# integration_test_board.net
KiCad netlist of a schematic drawn in EAGLE
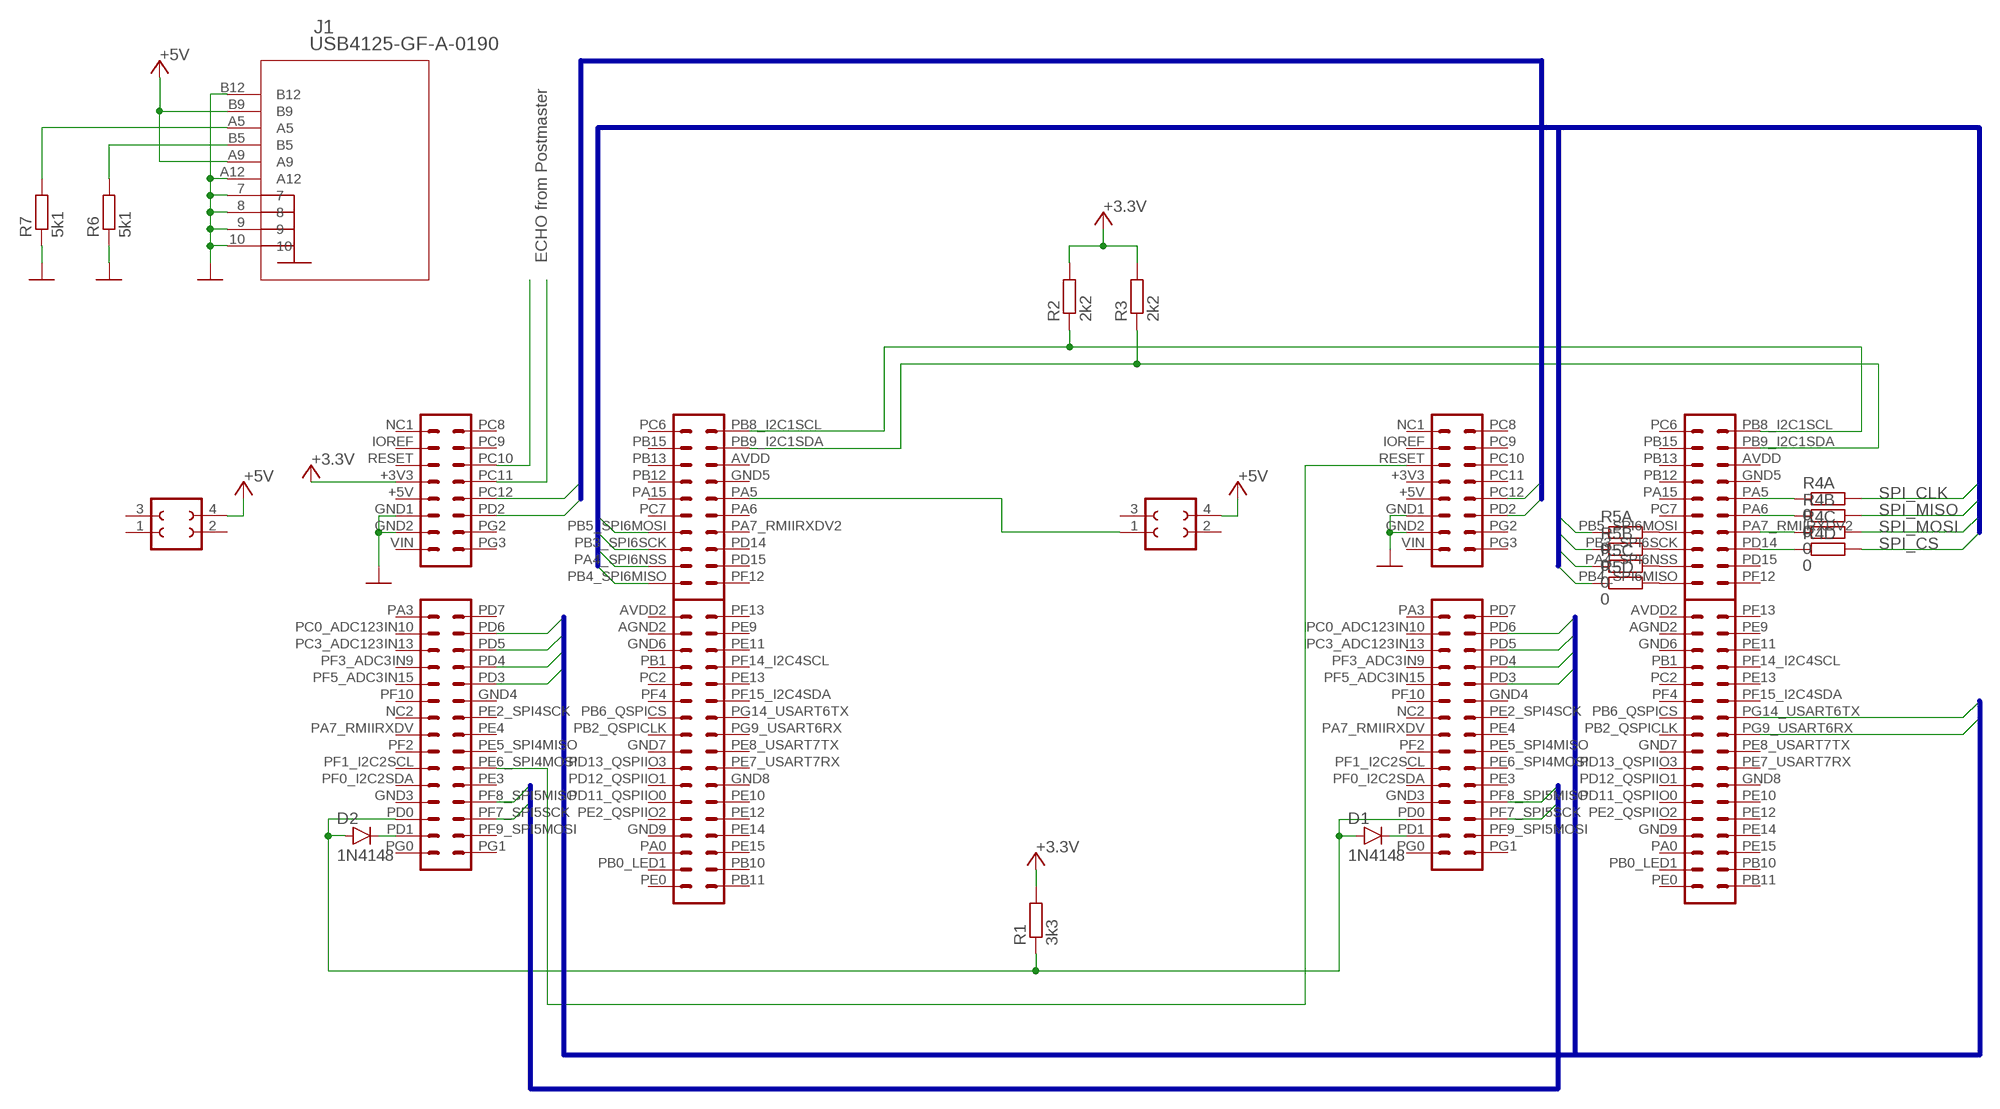
[diagram p0: schematic, sheet 1]

(export (version "E")
  (design (tool "Eeschema 10.0.6"))
  (components
    (comp (ref "D1")
      (value "1N4148")
      (footprint "eagle-import:MINIMELF")
      (libsource (lib "eagle-import") (part "1N4148"))
    )
    (comp (ref "D2")
      (value "1N4148")
      (footprint "eagle-import:MINIMELF")
      (libsource (lib "eagle-import") (part "1N4148"))
    )
    (comp (ref "J1")
      (value "USB4125-GF-A-0190")
      (footprint "eagle-import:CONN6_125-GF-A-0190_GCT")
      (fields (field (name "COPYRIGHT") "Copyright (C) 2023 Ultra Librarian. All rights reserved."))
      (libsource (lib "eagle-import") (part "USB4125-GF-A-0190"))
    )
    (comp (ref "R1")
      (value "3k3")
      (footprint "eagle-import:0805")
      (libsource (lib "eagle-import") (part "RESISTORR0805"))
    )
    (comp (ref "R2")
      (value "2k2")
      (footprint "eagle-import:0805")
      (libsource (lib "eagle-import") (part "RESISTORR0805"))
    )
    (comp (ref "R3")
      (value "2k2")
      (footprint "eagle-import:0805")
      (libsource (lib "eagle-import") (part "RESISTORR0805"))
    )
    (comp (ref "R4")
      (value "0")
      (footprint "eagle-import:ARRAY0603X4")
      (libsource (lib "eagle-import") (part "ARRAY-4RESISTOR"))
    )
    (comp (ref "R5")
      (value "0")
      (footprint "eagle-import:ARRAY0603X4")
      (libsource (lib "eagle-import") (part "ARRAY-4RESISTOR"))
    )
    (comp (ref "R6")
      (value "5k1")
      (footprint "eagle-import:0805")
      (libsource (lib "eagle-import") (part "RESISTORR0805"))
    )
    (comp (ref "R7")
      (value "5k1")
      (footprint "eagle-import:0805")
      (libsource (lib "eagle-import") (part "RESISTORR0805"))
    )
    (comp (ref "U$1")
      (value "NUCLEO-767")
      (footprint "eagle-import:NUCLEO-767")
      (libsource (lib "eagle-import") (part "NUCLEO-767"))
    )
    (comp (ref "U$2")
      (value "NUCLEO-767")
      (footprint "eagle-import:NUCLEO-767")
      (libsource (lib "eagle-import") (part "NUCLEO-767"))
    )
    (comp (ref "U$4")
      (value "HEADER-FEMALE-2-2")
      (footprint "eagle-import:HEADER-FEMALE-2-2")
      (libsource (lib "eagle-import") (part "HEADER-FEMALE-2-2"))
    )
    (comp (ref "U$5")
      (value "HEADER-FEMALE-2-2")
      (footprint "eagle-import:HEADER-FEMALE-2-2")
      (libsource (lib "eagle-import") (part "HEADER-FEMALE-2-2"))
    )
  )
  (nets
    (net (code "1") (name "+3.3V") (class "Default")
      (node (ref "R1") (pin "2") (pinfunction "2_2") (pintype "passive"))
      (node (ref "R2") (pin "2") (pinfunction "2_2") (pintype "passive"))
      (node (ref "R3") (pin "2") (pinfunction "2_2") (pintype "passive"))
      (node (ref "U$1") (pin "+3V3") (pinfunction "7_+3V3") (pintype "passive"))
    )
    (net (code "2") (name "+5V") (class "Default")
      (node (ref "J1") (pin "A9") (pinfunction "A9_A9") (pintype "passive"))
      (node (ref "J1") (pin "B9") (pinfunction "B9_B9") (pintype "passive"))
      (node (ref "U$4") (pin "4") (pinfunction "4_4") (pintype "passive"))
      (node (ref "U$5") (pin "4") (pinfunction "4_4") (pintype "passive"))
    )
    (net (code "3") (name "/ECHO_RX") (class "Default")
      (node (ref "U$1") (pin "PC12") (pinfunction "10_PC12") (pintype "passive"))
      (node (ref "U$2") (pin "PD2") (pinfunction "12_PD2") (pintype "passive"))
    )
    (net (code "4") (name "/ECHO_TX") (class "Default")
      (node (ref "U$1") (pin "PD2") (pinfunction "12_PD2") (pintype "passive"))
      (node (ref "U$2") (pin "PC12") (pinfunction "10_PC12") (pintype "passive"))
    )
    (net (code "5") (name "/GPIO_IN") (class "Default")
      (node (ref "U$1") (pin "PF7_SPI5SCK") (pinfunction "26_PF7_SPI5SCK") (pintype "passive"))
      (node (ref "U$2") (pin "PF7_SPI5SCK") (pinfunction "26_PF7_SPI5SCK") (pintype "passive"))
    )
    (net (code "6") (name "/GPIO_OUT") (class "Default")
      (node (ref "U$1") (pin "PF8_SPI5MISO") (pinfunction "24_PF8_SPI5MISO") (pintype "passive"))
      (node (ref "U$2") (pin "PF8_SPI5MISO") (pinfunction "24_PF8_SPI5MISO") (pintype "passive"))
    )
    (net (code "7") (name "/SPI_CLK") (class "Default")
      (node (ref "R4") (pin "8") (pinfunction "2_8") (pintype "passive"))
      (node (ref "R5") (pin "2") (pinfunction "1_2") (pintype "passive"))
      (node (ref "U$1") (pin "PB3_SPI6SCK") (pinfunction "15_PB3_SPI6SCK") (pintype "passive"))
    )
    (net (code "8") (name "/SPI_CS") (class "Default")
      (node (ref "R4") (pin "5") (pinfunction "2_5") (pintype "passive"))
      (node (ref "R5") (pin "3") (pinfunction "1_3") (pintype "passive"))
      (node (ref "U$1") (pin "PA4_SPI6NSS") (pinfunction "17_PA4_SPI6NSS") (pintype "passive"))
    )
    (net (code "9") (name "/SPI_MISO") (class "Default")
      (node (ref "R4") (pin "7") (pinfunction "2_7") (pintype "passive"))
      (node (ref "R5") (pin "4") (pinfunction "1_4") (pintype "passive"))
      (node (ref "U$1") (pin "PB4_SPI6MISO") (pinfunction "19_PB4_SPI6MISO") (pintype "passive"))
    )
    (net (code "10") (name "/SPI_MOSI") (class "Default")
      (node (ref "R4") (pin "6") (pinfunction "2_6") (pintype "passive"))
      (node (ref "R5") (pin "1") (pinfunction "1_1") (pintype "passive"))
      (node (ref "U$1") (pin "PB5_SPI6MOSI") (pinfunction "13_PB5_SPI6MOSI") (pintype "passive"))
    )
    (net (code "11") (name "/UART_CTS") (class "Default")
      (node (ref "U$1") (pin "PD4") (pinfunction "8_PD4") (pintype "passive"))
      (node (ref "U$2") (pin "PD3") (pinfunction "10_PD3") (pintype "passive"))
    )
    (net (code "12") (name "/UART_RTR") (class "Default")
      (node (ref "U$1") (pin "PD3") (pinfunction "10_PD3") (pintype "passive"))
      (node (ref "U$2") (pin "PD4") (pinfunction "8_PD4") (pintype "passive"))
    )
    (net (code "13") (name "/UART_RX") (class "Default")
      (node (ref "U$1") (pin "PD5") (pinfunction "6_PD5") (pintype "passive"))
      (node (ref "U$2") (pin "PD6") (pinfunction "4_PD6") (pintype "passive"))
      (node (ref "U$2") (pin "PG9_USART6RX") (pinfunction "16_PG9_USART6RX") (pintype "passive"))
    )
    (net (code "14") (name "/UART_TX") (class "Default")
      (node (ref "U$1") (pin "PD6") (pinfunction "4_PD6") (pintype "passive"))
      (node (ref "U$2") (pin "PD5") (pinfunction "6_PD5") (pintype "passive"))
      (node (ref "U$2") (pin "PG14_USART6TX") (pinfunction "14_PG14_USART6TX") (pintype "passive"))
    )
    (net (code "15") (name "0V") (class "Default")
      (node (ref "J1") (pin "10") (pinfunction "10_10") (pintype "passive"))
      (node (ref "J1") (pin "7") (pinfunction "7_7") (pintype "passive"))
      (node (ref "J1") (pin "8") (pinfunction "8_8") (pintype "passive"))
      (node (ref "J1") (pin "9") (pinfunction "9_9") (pintype "passive"))
      (node (ref "J1") (pin "A12") (pinfunction "A12_A12") (pintype "passive"))
      (node (ref "J1") (pin "B12") (pinfunction "B12_B12") (pintype "passive"))
      (node (ref "R6") (pin "1") (pinfunction "1_1") (pintype "passive"))
      (node (ref "R7") (pin "1") (pinfunction "1_1") (pintype "passive"))
      (node (ref "U$1") (pin "GND1") (pinfunction "11_GND1") (pintype "passive"))
      (node (ref "U$1") (pin "GND2") (pinfunction "13_GND2") (pintype "passive"))
      (node (ref "U$2") (pin "GND1") (pinfunction "11_GND1") (pintype "passive"))
      (node (ref "U$2") (pin "GND2") (pinfunction "13_GND2") (pintype "passive"))
    )
    (net (code "16") (name "Net-(J1-PadA5)") (class "Default")
      (node (ref "J1") (pin "A5") (pinfunction "A5_A5") (pintype "passive"))
      (node (ref "R7") (pin "2") (pinfunction "2_2") (pintype "passive"))
    )
    (net (code "17") (name "Net-(J1-PadB5)") (class "Default")
      (node (ref "J1") (pin "B5") (pinfunction "B5_B5") (pintype "passive"))
      (node (ref "R6") (pin "2") (pinfunction "2_2") (pintype "passive"))
    )
    (net (code "18") (name "Net-(R4B-1)") (class "Default")
      (node (ref "R4") (pin "2") (pinfunction "1_2") (pintype "passive"))
      (node (ref "U$2") (pin "PA6") (pinfunction "12_PA6") (pintype "passive"))
    )
    (net (code "19") (name "Net-(R4C-1)") (class "Default")
      (node (ref "R4") (pin "3") (pinfunction "1_3") (pintype "passive"))
      (node (ref "U$2") (pin "PA7_RMIIRXDV2") (pinfunction "14_PA7_RMIIRXDV2") (pintype "passive"))
    )
    (net (code "20") (name "Net-(R4D-1)") (class "Default")
      (node (ref "R4") (pin "4") (pinfunction "1_4") (pintype "passive"))
      (node (ref "U$2") (pin "PD14") (pinfunction "16_PD14") (pintype "passive"))
    )
    (net (code "21") (name "Net-(R5A-2)") (class "Default")
      (node (ref "R5") (pin "8") (pinfunction "2_8") (pintype "passive"))
      (node (ref "U$2") (pin "PB5_SPI6MOSI") (pinfunction "13_PB5_SPI6MOSI") (pintype "passive"))
    )
    (net (code "22") (name "Net-(R5B-2)") (class "Default")
      (node (ref "R5") (pin "7") (pinfunction "2_7") (pintype "passive"))
      (node (ref "U$2") (pin "PB3_SPI6SCK") (pinfunction "15_PB3_SPI6SCK") (pintype "passive"))
    )
    (net (code "23") (name "Net-(R5C-2)") (class "Default")
      (node (ref "R5") (pin "6") (pinfunction "2_6") (pintype "passive"))
      (node (ref "U$2") (pin "PA4_SPI6NSS") (pinfunction "17_PA4_SPI6NSS") (pintype "passive"))
    )
    (net (code "24") (name "Net-(R5D-2)") (class "Default")
      (node (ref "R5") (pin "5") (pinfunction "2_5") (pintype "passive"))
      (node (ref "U$2") (pin "PB4_SPI6MISO") (pinfunction "19_PB4_SPI6MISO") (pintype "passive"))
    )
    (net (code "25") (name "Net-(U$1B-20)") (class "Default")
      (node (ref "U$1") (pin "PE6_SPI4MOSI") (pinfunction "20_PE6_SPI4MOSI") (pintype "passive"))
      (node (ref "U$2") (pin "RESET") (pinfunction "5_RESET") (pintype "passive"))
    )
    (net (code "26") (name "Net-(U$1B-25)") (class "Default")
      (node (ref "D1") (pin "A") (pinfunction "A_A") (pintype "passive"))
      (node (ref "D2") (pin "A") (pinfunction "A_A") (pintype "passive"))
      (node (ref "R1") (pin "1") (pinfunction "1_1") (pintype "passive"))
      (node (ref "U$1") (pin "PD0") (pinfunction "25_PD0") (pintype "passive"))
      (node (ref "U$2") (pin "PD0") (pinfunction "25_PD0") (pintype "passive"))
    )
    (net (code "27") (name "Net-(U$1B-27)") (class "Default")
      (node (ref "D2") (pin "C") (pinfunction "C_C") (pintype "passive"))
      (node (ref "U$1") (pin "PD1") (pinfunction "27_PD1") (pintype "passive"))
    )
    (net (code "28") (name "Net-(U$1C-2)") (class "Default")
      (node (ref "R2") (pin "1") (pinfunction "1_1") (pintype "passive"))
      (node (ref "U$1") (pin "PB8_I2C1SCL") (pinfunction "2_PB8_I2C1SCL") (pintype "passive"))
      (node (ref "U$2") (pin "PB8_I2C1SCL") (pinfunction "2_PB8_I2C1SCL") (pintype "passive"))
    )
    (net (code "29") (name "Net-(U$1C-4)") (class "Default")
      (node (ref "R3") (pin "1") (pinfunction "1_1") (pintype "passive"))
      (node (ref "U$1") (pin "PB9_I2C1SDA") (pinfunction "4_PB9_I2C1SDA") (pintype "passive"))
      (node (ref "U$2") (pin "PB9_I2C1SDA") (pinfunction "4_PB9_I2C1SDA") (pintype "passive"))
    )
    (net (code "30") (name "Net-(U$1C-10)") (class "Default")
      (node (ref "U$1") (pin "PA5") (pinfunction "10_PA5") (pintype "passive"))
      (node (ref "U$4") (pin "1") (pinfunction "1_1") (pintype "passive"))
    )
    (net (code "31") (name "Net-(U$2B-27)") (class "Default")
      (node (ref "D1") (pin "C") (pinfunction "C_C") (pintype "passive"))
      (node (ref "U$2") (pin "PD1") (pinfunction "27_PD1") (pintype "passive"))
    )
    (net (code "32") (name "Net-(U$2C-10)") (class "Default")
      (node (ref "R4") (pin "1") (pinfunction "1_1") (pintype "passive"))
      (node (ref "U$2") (pin "PA5") (pinfunction "10_PA5") (pintype "passive"))
    )
    (net (code "33") (name "unconnected-(U$1A-1-PadNC1)") (class "Default")
      (node (ref "U$1") (pin "NC1") (pinfunction "1_NC1") (pintype "passive"))
    )
    (net (code "34") (name "unconnected-(U$1A-2-PadPC8)") (class "Default")
      (node (ref "U$1") (pin "PC8") (pinfunction "2_PC8") (pintype "passive"))
    )
    (net (code "35") (name "unconnected-(U$1A-3-PadIOREF)") (class "Default")
      (node (ref "U$1") (pin "IOREF") (pinfunction "3_IOREF") (pintype "passive"))
    )
    (net (code "36") (name "unconnected-(U$1A-4-PadPC9)") (class "Default")
      (node (ref "U$1") (pin "PC9") (pinfunction "4_PC9") (pintype "passive"))
    )
    (net (code "37") (name "unconnected-(U$1A-5-PadRESET)") (class "Default")
      (node (ref "U$1") (pin "RESET") (pinfunction "5_RESET") (pintype "passive"))
    )
    (net (code "38") (name "unconnected-(U$1A-6-PadPC10)") (class "Default")
      (node (ref "U$1") (pin "PC10") (pinfunction "6_PC10") (pintype "passive"))
    )
    (net (code "39") (name "unconnected-(U$1A-8-PadPC11)") (class "Default")
      (node (ref "U$1") (pin "PC11") (pinfunction "8_PC11") (pintype "passive"))
    )
    (net (code "40") (name "unconnected-(U$1A-9-Pad+5V)") (class "Default")
      (node (ref "U$1") (pin "+5V") (pinfunction "9_+5V") (pintype "passive"))
    )
    (net (code "41") (name "unconnected-(U$1A-14-PadPG2)") (class "Default")
      (node (ref "U$1") (pin "PG2") (pinfunction "14_PG2") (pintype "passive"))
    )
    (net (code "42") (name "unconnected-(U$1A-15-PadVIN)") (class "Default")
      (node (ref "U$1") (pin "VIN") (pinfunction "15_VIN") (pintype "passive"))
    )
    (net (code "43") (name "unconnected-(U$1A-16-PadPG3)") (class "Default")
      (node (ref "U$1") (pin "PG3") (pinfunction "16_PG3") (pintype "passive"))
    )
    (net (code "44") (name "unconnected-(U$1B-1-PadPA3)") (class "Default")
      (node (ref "U$1") (pin "PA3") (pinfunction "1_PA3") (pintype "passive"))
    )
    (net (code "45") (name "unconnected-(U$1B-2-PadPD7)") (class "Default")
      (node (ref "U$1") (pin "PD7") (pinfunction "2_PD7") (pintype "passive"))
    )
    (net (code "46") (name "unconnected-(U$1B-3-PadPC0_ADC123IN10)") (class "Default")
      (node (ref "U$1") (pin "PC0_ADC123IN10") (pinfunction "3_PC0_ADC123IN10") (pintype "passive"))
    )
    (net (code "47") (name "unconnected-(U$1B-5-PadPC3_ADC123IN13)") (class "Default")
      (node (ref "U$1") (pin "PC3_ADC123IN13") (pinfunction "5_PC3_ADC123IN13") (pintype "passive"))
    )
    (net (code "48") (name "unconnected-(U$1B-7-PadPF3_ADC3IN9)") (class "Default")
      (node (ref "U$1") (pin "PF3_ADC3IN9") (pinfunction "7_PF3_ADC3IN9") (pintype "passive"))
    )
    (net (code "49") (name "unconnected-(U$1B-9-PadPF5_ADC3IN15)") (class "Default")
      (node (ref "U$1") (pin "PF5_ADC3IN15") (pinfunction "9_PF5_ADC3IN15") (pintype "passive"))
    )
    (net (code "50") (name "unconnected-(U$1B-11-PadPF10)") (class "Default")
      (node (ref "U$1") (pin "PF10") (pinfunction "11_PF10") (pintype "passive"))
    )
    (net (code "51") (name "unconnected-(U$1B-12-PadGND4)") (class "Default")
      (node (ref "U$1") (pin "GND4") (pinfunction "12_GND4") (pintype "passive"))
    )
    (net (code "52") (name "unconnected-(U$1B-13-PadNC2)") (class "Default")
      (node (ref "U$1") (pin "NC2") (pinfunction "13_NC2") (pintype "passive"))
    )
    (net (code "53") (name "unconnected-(U$1B-14-PadPE2_SPI4SCK)") (class "Default")
      (node (ref "U$1") (pin "PE2_SPI4SCK") (pinfunction "14_PE2_SPI4SCK") (pintype "passive"))
    )
    (net (code "54") (name "unconnected-(U$1B-15-PadPA7_RMIIRXDV)") (class "Default")
      (node (ref "U$1") (pin "PA7_RMIIRXDV") (pinfunction "15_PA7_RMIIRXDV") (pintype "passive"))
    )
    (net (code "55") (name "unconnected-(U$1B-16-PadPE4)") (class "Default")
      (node (ref "U$1") (pin "PE4") (pinfunction "16_PE4") (pintype "passive"))
    )
    (net (code "56") (name "unconnected-(U$1B-17-PadPF2)") (class "Default")
      (node (ref "U$1") (pin "PF2") (pinfunction "17_PF2") (pintype "passive"))
    )
    (net (code "57") (name "unconnected-(U$1B-18-PadPE5_SPI4MISO)") (class "Default")
      (node (ref "U$1") (pin "PE5_SPI4MISO") (pinfunction "18_PE5_SPI4MISO") (pintype "passive"))
    )
    (net (code "58") (name "unconnected-(U$1B-19-PadPF1_I2C2SCL)") (class "Default")
      (node (ref "U$1") (pin "PF1_I2C2SCL") (pinfunction "19_PF1_I2C2SCL") (pintype "passive"))
    )
    (net (code "59") (name "unconnected-(U$1B-21-PadPF0_I2C2SDA)") (class "Default")
      (node (ref "U$1") (pin "PF0_I2C2SDA") (pinfunction "21_PF0_I2C2SDA") (pintype "passive"))
    )
    (net (code "60") (name "unconnected-(U$1B-22-PadPE3)") (class "Default")
      (node (ref "U$1") (pin "PE3") (pinfunction "22_PE3") (pintype "passive"))
    )
    (net (code "61") (name "unconnected-(U$1B-23-PadGND3)") (class "Default")
      (node (ref "U$1") (pin "GND3") (pinfunction "23_GND3") (pintype "passive"))
    )
    (net (code "62") (name "unconnected-(U$1B-28-PadPF9_SPI5MOSI)") (class "Default")
      (node (ref "U$1") (pin "PF9_SPI5MOSI") (pinfunction "28_PF9_SPI5MOSI") (pintype "passive"))
    )
    (net (code "63") (name "unconnected-(U$1B-29-PadPG0)") (class "Default")
      (node (ref "U$1") (pin "PG0") (pinfunction "29_PG0") (pintype "passive"))
    )
    (net (code "64") (name "unconnected-(U$1B-30-PadPG1)") (class "Default")
      (node (ref "U$1") (pin "PG1") (pinfunction "30_PG1") (pintype "passive"))
    )
    (net (code "65") (name "unconnected-(U$1C-1-PadPC6)") (class "Default")
      (node (ref "U$1") (pin "PC6") (pinfunction "1_PC6") (pintype "passive"))
    )
    (net (code "66") (name "unconnected-(U$1C-3-PadPB15)") (class "Default")
      (node (ref "U$1") (pin "PB15") (pinfunction "3_PB15") (pintype "passive"))
    )
    (net (code "67") (name "unconnected-(U$1C-5-PadPB13)") (class "Default")
      (node (ref "U$1") (pin "PB13") (pinfunction "5_PB13") (pintype "passive"))
    )
    (net (code "68") (name "unconnected-(U$1C-6-PadAVDD)") (class "Default")
      (node (ref "U$1") (pin "AVDD") (pinfunction "6_AVDD") (pintype "passive"))
    )
    (net (code "69") (name "unconnected-(U$1C-7-PadPB12)") (class "Default")
      (node (ref "U$1") (pin "PB12") (pinfunction "7_PB12") (pintype "passive"))
    )
    (net (code "70") (name "unconnected-(U$1C-8-PadGND5)") (class "Default")
      (node (ref "U$1") (pin "GND5") (pinfunction "8_GND5") (pintype "passive"))
    )
    (net (code "71") (name "unconnected-(U$1C-9-PadPA15)") (class "Default")
      (node (ref "U$1") (pin "PA15") (pinfunction "9_PA15") (pintype "passive"))
    )
    (net (code "72") (name "unconnected-(U$1C-11-PadPC7)") (class "Default")
      (node (ref "U$1") (pin "PC7") (pinfunction "11_PC7") (pintype "passive"))
    )
    (net (code "73") (name "unconnected-(U$1C-12-PadPA6)") (class "Default")
      (node (ref "U$1") (pin "PA6") (pinfunction "12_PA6") (pintype "passive"))
    )
    (net (code "74") (name "unconnected-(U$1C-14-PadPA7_RMIIRXDV2)") (class "Default")
      (node (ref "U$1") (pin "PA7_RMIIRXDV2") (pinfunction "14_PA7_RMIIRXDV2") (pintype "passive"))
    )
    (net (code "75") (name "unconnected-(U$1C-16-PadPD14)") (class "Default")
      (node (ref "U$1") (pin "PD14") (pinfunction "16_PD14") (pintype "passive"))
    )
    (net (code "76") (name "unconnected-(U$1C-18-PadPD15)") (class "Default")
      (node (ref "U$1") (pin "PD15") (pinfunction "18_PD15") (pintype "passive"))
    )
    (net (code "77") (name "unconnected-(U$1C-20-PadPF12)") (class "Default")
      (node (ref "U$1") (pin "PF12") (pinfunction "20_PF12") (pintype "passive"))
    )
    (net (code "78") (name "unconnected-(U$1D-1-PadAVDD2)") (class "Default")
      (node (ref "U$1") (pin "AVDD2") (pinfunction "1_AVDD2") (pintype "passive"))
    )
    (net (code "79") (name "unconnected-(U$1D-2-PadPF13)") (class "Default")
      (node (ref "U$1") (pin "PF13") (pinfunction "2_PF13") (pintype "passive"))
    )
    (net (code "80") (name "unconnected-(U$1D-3-PadAGND2)") (class "Default")
      (node (ref "U$1") (pin "AGND2") (pinfunction "3_AGND2") (pintype "passive"))
    )
    (net (code "81") (name "unconnected-(U$1D-4-PadPE9)") (class "Default")
      (node (ref "U$1") (pin "PE9") (pinfunction "4_PE9") (pintype "passive"))
    )
    (net (code "82") (name "unconnected-(U$1D-5-PadGND6)") (class "Default")
      (node (ref "U$1") (pin "GND6") (pinfunction "5_GND6") (pintype "passive"))
    )
    (net (code "83") (name "unconnected-(U$1D-6-PadPE11)") (class "Default")
      (node (ref "U$1") (pin "PE11") (pinfunction "6_PE11") (pintype "passive"))
    )
    (net (code "84") (name "unconnected-(U$1D-7-PadPB1)") (class "Default")
      (node (ref "U$1") (pin "PB1") (pinfunction "7_PB1") (pintype "passive"))
    )
    (net (code "85") (name "unconnected-(U$1D-8-PadPF14_I2C4SCL)") (class "Default")
      (node (ref "U$1") (pin "PF14_I2C4SCL") (pinfunction "8_PF14_I2C4SCL") (pintype "passive"))
    )
    (net (code "86") (name "unconnected-(U$1D-9-PadPC2)") (class "Default")
      (node (ref "U$1") (pin "PC2") (pinfunction "9_PC2") (pintype "passive"))
    )
    (net (code "87") (name "unconnected-(U$1D-10-PadPE13)") (class "Default")
      (node (ref "U$1") (pin "PE13") (pinfunction "10_PE13") (pintype "passive"))
    )
    (net (code "88") (name "unconnected-(U$1D-11-PadPF4)") (class "Default")
      (node (ref "U$1") (pin "PF4") (pinfunction "11_PF4") (pintype "passive"))
    )
    (net (code "89") (name "unconnected-(U$1D-12-PadPF15_I2C4SDA)") (class "Default")
      (node (ref "U$1") (pin "PF15_I2C4SDA") (pinfunction "12_PF15_I2C4SDA") (pintype "passive"))
    )
    (net (code "90") (name "unconnected-(U$1D-13-PadPB6_QSPICS)") (class "Default")
      (node (ref "U$1") (pin "PB6_QSPICS") (pinfunction "13_PB6_QSPICS") (pintype "passive"))
    )
    (net (code "91") (name "unconnected-(U$1D-14-PadPG14_USART6TX)") (class "Default")
      (node (ref "U$1") (pin "PG14_USART6TX") (pinfunction "14_PG14_USART6TX") (pintype "passive"))
    )
    (net (code "92") (name "unconnected-(U$1D-15-PadPB2_QSPICLK)") (class "Default")
      (node (ref "U$1") (pin "PB2_QSPICLK") (pinfunction "15_PB2_QSPICLK") (pintype "passive"))
    )
    (net (code "93") (name "unconnected-(U$1D-16-PadPG9_USART6RX)") (class "Default")
      (node (ref "U$1") (pin "PG9_USART6RX") (pinfunction "16_PG9_USART6RX") (pintype "passive"))
    )
    (net (code "94") (name "unconnected-(U$1D-17-PadGND7)") (class "Default")
      (node (ref "U$1") (pin "GND7") (pinfunction "17_GND7") (pintype "passive"))
    )
    (net (code "95") (name "unconnected-(U$1D-18-PadPE8_USART7TX)") (class "Default")
      (node (ref "U$1") (pin "PE8_USART7TX") (pinfunction "18_PE8_USART7TX") (pintype "passive"))
    )
    (net (code "96") (name "unconnected-(U$1D-19-PadPD13_QSPIIO3)") (class "Default")
      (node (ref "U$1") (pin "PD13_QSPIIO3") (pinfunction "19_PD13_QSPIIO3") (pintype "passive"))
    )
    (net (code "97") (name "unconnected-(U$1D-20-PadPE7_USART7RX)") (class "Default")
      (node (ref "U$1") (pin "PE7_USART7RX") (pinfunction "20_PE7_USART7RX") (pintype "passive"))
    )
    (net (code "98") (name "unconnected-(U$1D-21-PadPD12_QSPIIO1)") (class "Default")
      (node (ref "U$1") (pin "PD12_QSPIIO1") (pinfunction "21_PD12_QSPIIO1") (pintype "passive"))
    )
    (net (code "99") (name "unconnected-(U$1D-22-PadGND8)") (class "Default")
      (node (ref "U$1") (pin "GND8") (pinfunction "22_GND8") (pintype "passive"))
    )
    (net (code "100") (name "unconnected-(U$1D-23-PadPD11_QSPIIO0)") (class "Default")
      (node (ref "U$1") (pin "PD11_QSPIIO0") (pinfunction "23_PD11_QSPIIO0") (pintype "passive"))
    )
    (net (code "101") (name "unconnected-(U$1D-24-PadPE10)") (class "Default")
      (node (ref "U$1") (pin "PE10") (pinfunction "24_PE10") (pintype "passive"))
    )
    (net (code "102") (name "unconnected-(U$1D-25-PadPE2_QSPIIO2)") (class "Default")
      (node (ref "U$1") (pin "PE2_QSPIIO2") (pinfunction "25_PE2_QSPIIO2") (pintype "passive"))
    )
    (net (code "103") (name "unconnected-(U$1D-26-PadPE12)") (class "Default")
      (node (ref "U$1") (pin "PE12") (pinfunction "26_PE12") (pintype "passive"))
    )
    (net (code "104") (name "unconnected-(U$1D-27-PadGND9)") (class "Default")
      (node (ref "U$1") (pin "GND9") (pinfunction "27_GND9") (pintype "passive"))
    )
    (net (code "105") (name "unconnected-(U$1D-28-PadPE14)") (class "Default")
      (node (ref "U$1") (pin "PE14") (pinfunction "28_PE14") (pintype "passive"))
    )
    (net (code "106") (name "unconnected-(U$1D-29-PadPA0)") (class "Default")
      (node (ref "U$1") (pin "PA0") (pinfunction "29_PA0") (pintype "passive"))
    )
    (net (code "107") (name "unconnected-(U$1D-30-PadPE15)") (class "Default")
      (node (ref "U$1") (pin "PE15") (pinfunction "30_PE15") (pintype "passive"))
    )
    (net (code "108") (name "unconnected-(U$1D-31-PadPB0_LED1)") (class "Default")
      (node (ref "U$1") (pin "PB0_LED1") (pinfunction "31_PB0_LED1") (pintype "passive"))
    )
    (net (code "109") (name "unconnected-(U$1D-32-PadPB10)") (class "Default")
      (node (ref "U$1") (pin "PB10") (pinfunction "32_PB10") (pintype "passive"))
    )
    (net (code "110") (name "unconnected-(U$1D-33-PadPE0)") (class "Default")
      (node (ref "U$1") (pin "PE0") (pinfunction "33_PE0") (pintype "passive"))
    )
    (net (code "111") (name "unconnected-(U$1D-34-PadPB11)") (class "Default")
      (node (ref "U$1") (pin "PB11") (pinfunction "34_PB11") (pintype "passive"))
    )
    (net (code "112") (name "unconnected-(U$2A-1-PadNC1)") (class "Default")
      (node (ref "U$2") (pin "NC1") (pinfunction "1_NC1") (pintype "passive"))
    )
    (net (code "113") (name "unconnected-(U$2A-2-PadPC8)") (class "Default")
      (node (ref "U$2") (pin "PC8") (pinfunction "2_PC8") (pintype "passive"))
    )
    (net (code "114") (name "unconnected-(U$2A-3-PadIOREF)") (class "Default")
      (node (ref "U$2") (pin "IOREF") (pinfunction "3_IOREF") (pintype "passive"))
    )
    (net (code "115") (name "unconnected-(U$2A-4-PadPC9)") (class "Default")
      (node (ref "U$2") (pin "PC9") (pinfunction "4_PC9") (pintype "passive"))
    )
    (net (code "116") (name "unconnected-(U$2A-6-PadPC10)") (class "Default")
      (node (ref "U$2") (pin "PC10") (pinfunction "6_PC10") (pintype "passive"))
    )
    (net (code "117") (name "unconnected-(U$2A-7-Pad+3V3)") (class "Default")
      (node (ref "U$2") (pin "+3V3") (pinfunction "7_+3V3") (pintype "passive"))
    )
    (net (code "118") (name "unconnected-(U$2A-8-PadPC11)") (class "Default")
      (node (ref "U$2") (pin "PC11") (pinfunction "8_PC11") (pintype "passive"))
    )
    (net (code "119") (name "unconnected-(U$2A-9-Pad+5V)") (class "Default")
      (node (ref "U$2") (pin "+5V") (pinfunction "9_+5V") (pintype "passive"))
    )
    (net (code "120") (name "unconnected-(U$2A-14-PadPG2)") (class "Default")
      (node (ref "U$2") (pin "PG2") (pinfunction "14_PG2") (pintype "passive"))
    )
    (net (code "121") (name "unconnected-(U$2A-15-PadVIN)") (class "Default")
      (node (ref "U$2") (pin "VIN") (pinfunction "15_VIN") (pintype "passive"))
    )
    (net (code "122") (name "unconnected-(U$2A-16-PadPG3)") (class "Default")
      (node (ref "U$2") (pin "PG3") (pinfunction "16_PG3") (pintype "passive"))
    )
    (net (code "123") (name "unconnected-(U$2B-1-PadPA3)") (class "Default")
      (node (ref "U$2") (pin "PA3") (pinfunction "1_PA3") (pintype "passive"))
    )
    (net (code "124") (name "unconnected-(U$2B-2-PadPD7)") (class "Default")
      (node (ref "U$2") (pin "PD7") (pinfunction "2_PD7") (pintype "passive"))
    )
    (net (code "125") (name "unconnected-(U$2B-3-PadPC0_ADC123IN10)") (class "Default")
      (node (ref "U$2") (pin "PC0_ADC123IN10") (pinfunction "3_PC0_ADC123IN10") (pintype "passive"))
    )
    (net (code "126") (name "unconnected-(U$2B-5-PadPC3_ADC123IN13)") (class "Default")
      (node (ref "U$2") (pin "PC3_ADC123IN13") (pinfunction "5_PC3_ADC123IN13") (pintype "passive"))
    )
    (net (code "127") (name "unconnected-(U$2B-7-PadPF3_ADC3IN9)") (class "Default")
      (node (ref "U$2") (pin "PF3_ADC3IN9") (pinfunction "7_PF3_ADC3IN9") (pintype "passive"))
    )
    (net (code "128") (name "unconnected-(U$2B-9-PadPF5_ADC3IN15)") (class "Default")
      (node (ref "U$2") (pin "PF5_ADC3IN15") (pinfunction "9_PF5_ADC3IN15") (pintype "passive"))
    )
    (net (code "129") (name "unconnected-(U$2B-11-PadPF10)") (class "Default")
      (node (ref "U$2") (pin "PF10") (pinfunction "11_PF10") (pintype "passive"))
    )
    (net (code "130") (name "unconnected-(U$2B-12-PadGND4)") (class "Default")
      (node (ref "U$2") (pin "GND4") (pinfunction "12_GND4") (pintype "passive"))
    )
    (net (code "131") (name "unconnected-(U$2B-13-PadNC2)") (class "Default")
      (node (ref "U$2") (pin "NC2") (pinfunction "13_NC2") (pintype "passive"))
    )
    (net (code "132") (name "unconnected-(U$2B-14-PadPE2_SPI4SCK)") (class "Default")
      (node (ref "U$2") (pin "PE2_SPI4SCK") (pinfunction "14_PE2_SPI4SCK") (pintype "passive"))
    )
    (net (code "133") (name "unconnected-(U$2B-15-PadPA7_RMIIRXDV)") (class "Default")
      (node (ref "U$2") (pin "PA7_RMIIRXDV") (pinfunction "15_PA7_RMIIRXDV") (pintype "passive"))
    )
    (net (code "134") (name "unconnected-(U$2B-16-PadPE4)") (class "Default")
      (node (ref "U$2") (pin "PE4") (pinfunction "16_PE4") (pintype "passive"))
    )
    (net (code "135") (name "unconnected-(U$2B-17-PadPF2)") (class "Default")
      (node (ref "U$2") (pin "PF2") (pinfunction "17_PF2") (pintype "passive"))
    )
    (net (code "136") (name "unconnected-(U$2B-18-PadPE5_SPI4MISO)") (class "Default")
      (node (ref "U$2") (pin "PE5_SPI4MISO") (pinfunction "18_PE5_SPI4MISO") (pintype "passive"))
    )
    (net (code "137") (name "unconnected-(U$2B-19-PadPF1_I2C2SCL)") (class "Default")
      (node (ref "U$2") (pin "PF1_I2C2SCL") (pinfunction "19_PF1_I2C2SCL") (pintype "passive"))
    )
    (net (code "138") (name "unconnected-(U$2B-20-PadPE6_SPI4MOSI)") (class "Default")
      (node (ref "U$2") (pin "PE6_SPI4MOSI") (pinfunction "20_PE6_SPI4MOSI") (pintype "passive"))
    )
    (net (code "139") (name "unconnected-(U$2B-21-PadPF0_I2C2SDA)") (class "Default")
      (node (ref "U$2") (pin "PF0_I2C2SDA") (pinfunction "21_PF0_I2C2SDA") (pintype "passive"))
    )
    (net (code "140") (name "unconnected-(U$2B-22-PadPE3)") (class "Default")
      (node (ref "U$2") (pin "PE3") (pinfunction "22_PE3") (pintype "passive"))
    )
    (net (code "141") (name "unconnected-(U$2B-23-PadGND3)") (class "Default")
      (node (ref "U$2") (pin "GND3") (pinfunction "23_GND3") (pintype "passive"))
    )
    (net (code "142") (name "unconnected-(U$2B-28-PadPF9_SPI5MOSI)") (class "Default")
      (node (ref "U$2") (pin "PF9_SPI5MOSI") (pinfunction "28_PF9_SPI5MOSI") (pintype "passive"))
    )
    (net (code "143") (name "unconnected-(U$2B-29-PadPG0)") (class "Default")
      (node (ref "U$2") (pin "PG0") (pinfunction "29_PG0") (pintype "passive"))
    )
    (net (code "144") (name "unconnected-(U$2B-30-PadPG1)") (class "Default")
      (node (ref "U$2") (pin "PG1") (pinfunction "30_PG1") (pintype "passive"))
    )
    (net (code "145") (name "unconnected-(U$2C-1-PadPC6)") (class "Default")
      (node (ref "U$2") (pin "PC6") (pinfunction "1_PC6") (pintype "passive"))
    )
    (net (code "146") (name "unconnected-(U$2C-3-PadPB15)") (class "Default")
      (node (ref "U$2") (pin "PB15") (pinfunction "3_PB15") (pintype "passive"))
    )
    (net (code "147") (name "unconnected-(U$2C-5-PadPB13)") (class "Default")
      (node (ref "U$2") (pin "PB13") (pinfunction "5_PB13") (pintype "passive"))
    )
    (net (code "148") (name "unconnected-(U$2C-6-PadAVDD)") (class "Default")
      (node (ref "U$2") (pin "AVDD") (pinfunction "6_AVDD") (pintype "passive"))
    )
    (net (code "149") (name "unconnected-(U$2C-7-PadPB12)") (class "Default")
      (node (ref "U$2") (pin "PB12") (pinfunction "7_PB12") (pintype "passive"))
    )
    (net (code "150") (name "unconnected-(U$2C-8-PadGND5)") (class "Default")
      (node (ref "U$2") (pin "GND5") (pinfunction "8_GND5") (pintype "passive"))
    )
    (net (code "151") (name "unconnected-(U$2C-9-PadPA15)") (class "Default")
      (node (ref "U$2") (pin "PA15") (pinfunction "9_PA15") (pintype "passive"))
    )
    (net (code "152") (name "unconnected-(U$2C-11-PadPC7)") (class "Default")
      (node (ref "U$2") (pin "PC7") (pinfunction "11_PC7") (pintype "passive"))
    )
    (net (code "153") (name "unconnected-(U$2C-18-PadPD15)") (class "Default")
      (node (ref "U$2") (pin "PD15") (pinfunction "18_PD15") (pintype "passive"))
    )
    (net (code "154") (name "unconnected-(U$2C-20-PadPF12)") (class "Default")
      (node (ref "U$2") (pin "PF12") (pinfunction "20_PF12") (pintype "passive"))
    )
    (net (code "155") (name "unconnected-(U$2D-1-PadAVDD2)") (class "Default")
      (node (ref "U$2") (pin "AVDD2") (pinfunction "1_AVDD2") (pintype "passive"))
    )
    (net (code "156") (name "unconnected-(U$2D-2-PadPF13)") (class "Default")
      (node (ref "U$2") (pin "PF13") (pinfunction "2_PF13") (pintype "passive"))
    )
    (net (code "157") (name "unconnected-(U$2D-3-PadAGND2)") (class "Default")
      (node (ref "U$2") (pin "AGND2") (pinfunction "3_AGND2") (pintype "passive"))
    )
    (net (code "158") (name "unconnected-(U$2D-4-PadPE9)") (class "Default")
      (node (ref "U$2") (pin "PE9") (pinfunction "4_PE9") (pintype "passive"))
    )
    (net (code "159") (name "unconnected-(U$2D-5-PadGND6)") (class "Default")
      (node (ref "U$2") (pin "GND6") (pinfunction "5_GND6") (pintype "passive"))
    )
    (net (code "160") (name "unconnected-(U$2D-6-PadPE11)") (class "Default")
      (node (ref "U$2") (pin "PE11") (pinfunction "6_PE11") (pintype "passive"))
    )
    (net (code "161") (name "unconnected-(U$2D-7-PadPB1)") (class "Default")
      (node (ref "U$2") (pin "PB1") (pinfunction "7_PB1") (pintype "passive"))
    )
    (net (code "162") (name "unconnected-(U$2D-8-PadPF14_I2C4SCL)") (class "Default")
      (node (ref "U$2") (pin "PF14_I2C4SCL") (pinfunction "8_PF14_I2C4SCL") (pintype "passive"))
    )
    (net (code "163") (name "unconnected-(U$2D-9-PadPC2)") (class "Default")
      (node (ref "U$2") (pin "PC2") (pinfunction "9_PC2") (pintype "passive"))
    )
    (net (code "164") (name "unconnected-(U$2D-10-PadPE13)") (class "Default")
      (node (ref "U$2") (pin "PE13") (pinfunction "10_PE13") (pintype "passive"))
    )
    (net (code "165") (name "unconnected-(U$2D-11-PadPF4)") (class "Default")
      (node (ref "U$2") (pin "PF4") (pinfunction "11_PF4") (pintype "passive"))
    )
    (net (code "166") (name "unconnected-(U$2D-12-PadPF15_I2C4SDA)") (class "Default")
      (node (ref "U$2") (pin "PF15_I2C4SDA") (pinfunction "12_PF15_I2C4SDA") (pintype "passive"))
    )
    (net (code "167") (name "unconnected-(U$2D-13-PadPB6_QSPICS)") (class "Default")
      (node (ref "U$2") (pin "PB6_QSPICS") (pinfunction "13_PB6_QSPICS") (pintype "passive"))
    )
    (net (code "168") (name "unconnected-(U$2D-15-PadPB2_QSPICLK)") (class "Default")
      (node (ref "U$2") (pin "PB2_QSPICLK") (pinfunction "15_PB2_QSPICLK") (pintype "passive"))
    )
    (net (code "169") (name "unconnected-(U$2D-17-PadGND7)") (class "Default")
      (node (ref "U$2") (pin "GND7") (pinfunction "17_GND7") (pintype "passive"))
    )
    (net (code "170") (name "unconnected-(U$2D-18-PadPE8_USART7TX)") (class "Default")
      (node (ref "U$2") (pin "PE8_USART7TX") (pinfunction "18_PE8_USART7TX") (pintype "passive"))
    )
    (net (code "171") (name "unconnected-(U$2D-19-PadPD13_QSPIIO3)") (class "Default")
      (node (ref "U$2") (pin "PD13_QSPIIO3") (pinfunction "19_PD13_QSPIIO3") (pintype "passive"))
    )
    (net (code "172") (name "unconnected-(U$2D-20-PadPE7_USART7RX)") (class "Default")
      (node (ref "U$2") (pin "PE7_USART7RX") (pinfunction "20_PE7_USART7RX") (pintype "passive"))
    )
    (net (code "173") (name "unconnected-(U$2D-21-PadPD12_QSPIIO1)") (class "Default")
      (node (ref "U$2") (pin "PD12_QSPIIO1") (pinfunction "21_PD12_QSPIIO1") (pintype "passive"))
    )
    (net (code "174") (name "unconnected-(U$2D-22-PadGND8)") (class "Default")
      (node (ref "U$2") (pin "GND8") (pinfunction "22_GND8") (pintype "passive"))
    )
    (net (code "175") (name "unconnected-(U$2D-23-PadPD11_QSPIIO0)") (class "Default")
      (node (ref "U$2") (pin "PD11_QSPIIO0") (pinfunction "23_PD11_QSPIIO0") (pintype "passive"))
    )
    (net (code "176") (name "unconnected-(U$2D-24-PadPE10)") (class "Default")
      (node (ref "U$2") (pin "PE10") (pinfunction "24_PE10") (pintype "passive"))
    )
    (net (code "177") (name "unconnected-(U$2D-25-PadPE2_QSPIIO2)") (class "Default")
      (node (ref "U$2") (pin "PE2_QSPIIO2") (pinfunction "25_PE2_QSPIIO2") (pintype "passive"))
    )
    (net (code "178") (name "unconnected-(U$2D-26-PadPE12)") (class "Default")
      (node (ref "U$2") (pin "PE12") (pinfunction "26_PE12") (pintype "passive"))
    )
    (net (code "179") (name "unconnected-(U$2D-27-PadGND9)") (class "Default")
      (node (ref "U$2") (pin "GND9") (pinfunction "27_GND9") (pintype "passive"))
    )
    (net (code "180") (name "unconnected-(U$2D-28-PadPE14)") (class "Default")
      (node (ref "U$2") (pin "PE14") (pinfunction "28_PE14") (pintype "passive"))
    )
    (net (code "181") (name "unconnected-(U$2D-29-PadPA0)") (class "Default")
      (node (ref "U$2") (pin "PA0") (pinfunction "29_PA0") (pintype "passive"))
    )
    (net (code "182") (name "unconnected-(U$2D-30-PadPE15)") (class "Default")
      (node (ref "U$2") (pin "PE15") (pinfunction "30_PE15") (pintype "passive"))
    )
    (net (code "183") (name "unconnected-(U$2D-31-PadPB0_LED1)") (class "Default")
      (node (ref "U$2") (pin "PB0_LED1") (pinfunction "31_PB0_LED1") (pintype "passive"))
    )
    (net (code "184") (name "unconnected-(U$2D-32-PadPB10)") (class "Default")
      (node (ref "U$2") (pin "PB10") (pinfunction "32_PB10") (pintype "passive"))
    )
    (net (code "185") (name "unconnected-(U$2D-33-PadPE0)") (class "Default")
      (node (ref "U$2") (pin "PE0") (pinfunction "33_PE0") (pintype "passive"))
    )
    (net (code "186") (name "unconnected-(U$2D-34-PadPB11)") (class "Default")
      (node (ref "U$2") (pin "PB11") (pinfunction "34_PB11") (pintype "passive"))
    )
    (net (code "187") (name "unconnected-(U$4-Pad2)") (class "Default")
      (node (ref "U$4") (pin "2") (pinfunction "2_2") (pintype "passive"))
    )
    (net (code "188") (name "unconnected-(U$4-Pad3)") (class "Default")
      (node (ref "U$4") (pin "3") (pinfunction "3_3") (pintype "passive"))
    )
    (net (code "189") (name "unconnected-(U$5-Pad1)") (class "Default")
      (node (ref "U$5") (pin "1") (pinfunction "1_1") (pintype "passive"))
    )
    (net (code "190") (name "unconnected-(U$5-Pad2)") (class "Default")
      (node (ref "U$5") (pin "2") (pinfunction "2_2") (pintype "passive"))
    )
    (net (code "191") (name "unconnected-(U$5-Pad3)") (class "Default")
      (node (ref "U$5") (pin "3") (pinfunction "3_3") (pintype "passive"))
    )
  )
)
